# I2C_1.net
KiCad netlist of a schematic drawn in Altium Designer
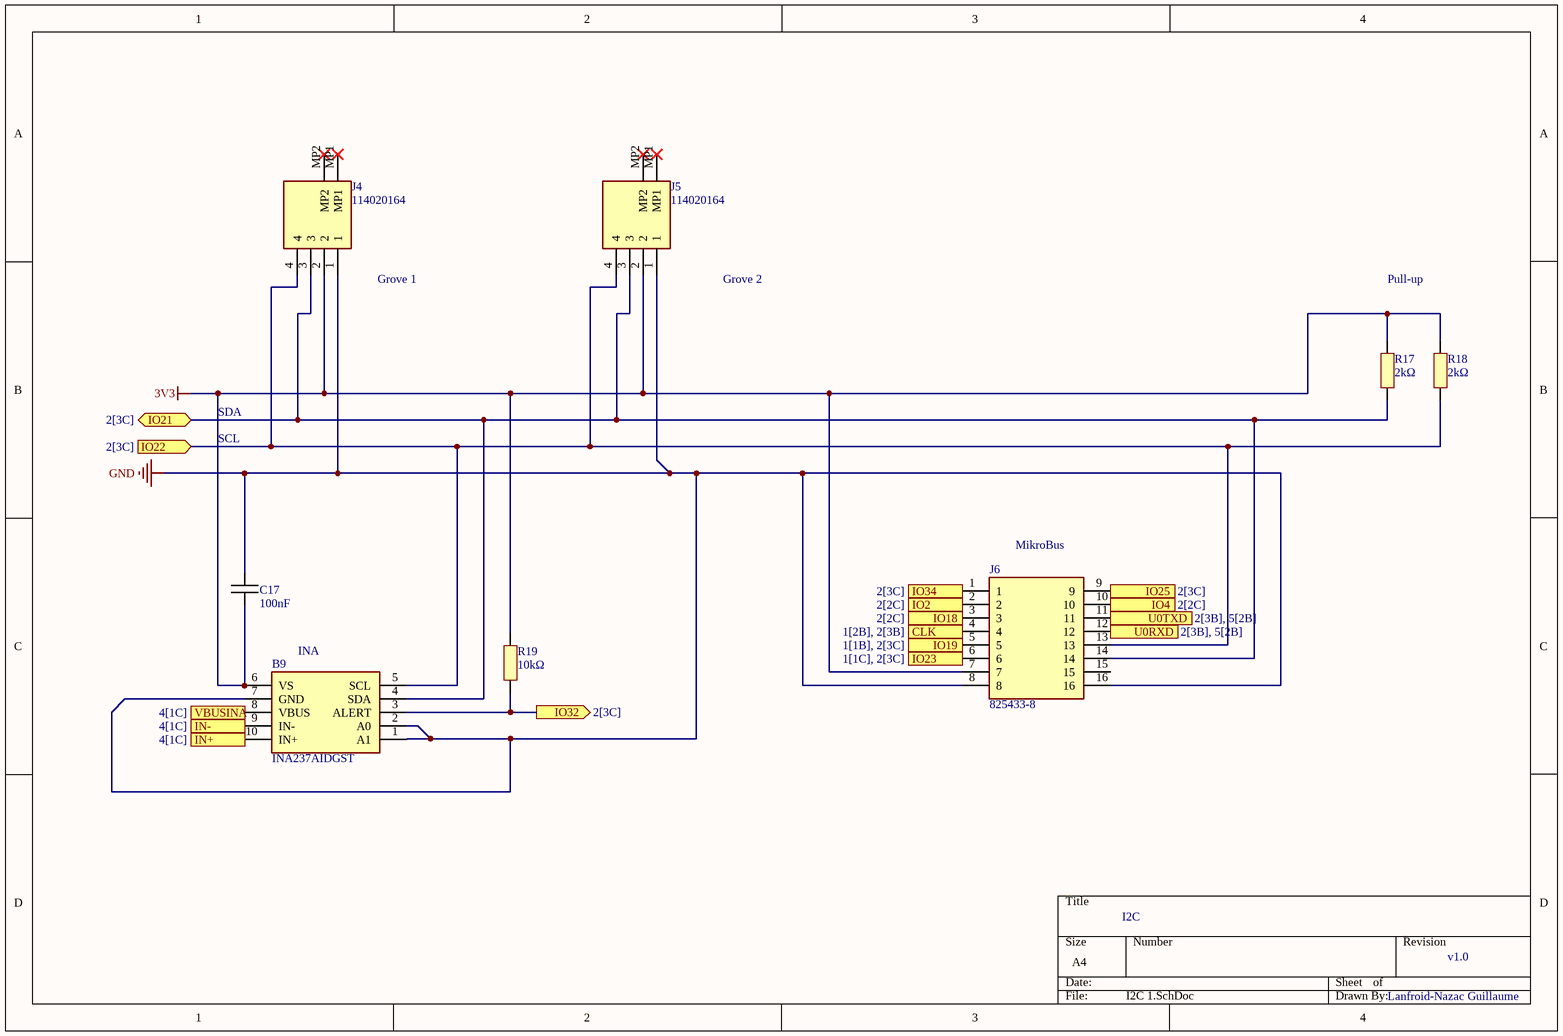
[diagram p0: I2C 1.SchDoc]

(export (version "E")
  (design (tool "Eeschema 10.0.6"))
  (components
    (comp (ref "B9")
      (value "INA237AIDGST")
      (footprint "SOP50P490X110-10N")
      (fields (field (name "MOUSER PART NUMBER") "595-INA237AIDGST"))
      (libsource (lib "SCHLibrary") (part "INA237AIDGST"))
    )
    (comp (ref "C17")
      (value "100nF")
      (footprint "CAPC1005X06N")
      (libsource (lib "SCHLibrary") (part "Capacitor"))
    )
    (comp (ref "J4")
      (value "114020164")
      (footprint "114020164")
      (description "Seeed Studio Accessories Grove Female Header - SMD-4P-2.0mm-90D-20Pcs")
      (fields (field (name "MOUSER PART NUMBER") "713-114020164"))
      (libsource (lib "SCHLibrary") (part "114020164"))
    )
    (comp (ref "J5")
      (value "114020164")
      (footprint "114020164")
      (description "Seeed Studio Accessories Grove Female Header - SMD-4P-2.0mm-90D-20Pcs")
      (fields (field (name "MOUSER PART NUMBER") "713-114020164"))
      (libsource (lib "SCHLibrary") (part "114020164"))
    )
    (comp (ref "J6")
      (value "825433-8")
      (footprint "Connect-Mikrobus")
      (description "Headers & Wire Housings 8P double for connection mikrobus")
      (fields (field (name "MOUSER PART NUMBER") "571-825433-8"))
      (libsource (lib "SCHLibrary") (part "Connect-Mikrobus"))
    )
    (comp (ref "R17")
      (value "2kΩ")
      (footprint "RESC1005X06N")
      (libsource (lib "SCHLibrary") (part "Resistor"))
    )
    (comp (ref "R18")
      (value "2kΩ")
      (footprint "RESC1005X06N")
      (libsource (lib "SCHLibrary") (part "Resistor"))
    )
    (comp (ref "R19")
      (value "10kΩ")
      (footprint "RESC1005X06N")
      (libsource (lib "SCHLibrary") (part "Resistor"))
    )
  )
  (nets
    (net (code "1") (name "/CLK") (class "Default")
      (node (ref "J6") (pin "4") (pinfunction "4_4") (pintype "passive"))
    )
    (net (code "2") (name "/IN+") (class "Default")
      (node (ref "B9") (pin "10") (pinfunction "IN+_10") (pintype "passive"))
    )
    (net (code "3") (name "/IN-") (class "Default")
      (node (ref "B9") (pin "9") (pinfunction "IN-_9") (pintype "passive"))
    )
    (net (code "4") (name "/IO2") (class "Default")
      (node (ref "J6") (pin "2") (pinfunction "2_2") (pintype "passive"))
    )
    (net (code "5") (name "/IO4") (class "Default")
      (node (ref "J6") (pin "10") (pinfunction "10_10") (pintype "passive"))
    )
    (net (code "6") (name "/IO18") (class "Default")
      (node (ref "J6") (pin "3") (pinfunction "3_3") (pintype "passive"))
    )
    (net (code "7") (name "/IO19") (class "Default")
      (node (ref "J6") (pin "5") (pinfunction "5_5") (pintype "passive"))
    )
    (net (code "8") (name "/IO21") (class "Default")
      (node (ref "B9") (pin "4") (pinfunction "SDA_4") (pintype "passive"))
      (node (ref "J4") (pin "3") (pinfunction "3_3") (pintype "passive"))
      (node (ref "J5") (pin "3") (pinfunction "3_3") (pintype "passive"))
      (node (ref "J6") (pin "14") (pinfunction "14_14") (pintype "passive"))
      (node (ref "R17") (pin "2") (pinfunction "2_2") (pintype "passive"))
    )
    (net (code "9") (name "/IO22") (class "Default")
      (node (ref "B9") (pin "5") (pinfunction "SCL_5") (pintype "passive"))
      (node (ref "J4") (pin "4") (pinfunction "4_4") (pintype "passive"))
      (node (ref "J5") (pin "4") (pinfunction "4_4") (pintype "passive"))
      (node (ref "J6") (pin "13") (pinfunction "13_13") (pintype "passive"))
      (node (ref "R18") (pin "2") (pinfunction "2_2") (pintype "passive"))
    )
    (net (code "10") (name "/IO23") (class "Default")
      (node (ref "J6") (pin "6") (pinfunction "6_6") (pintype "passive"))
    )
    (net (code "11") (name "/IO25") (class "Default")
      (node (ref "J6") (pin "9") (pinfunction "9_9") (pintype "passive"))
    )
    (net (code "12") (name "/IO32") (class "Default")
      (node (ref "B9") (pin "3") (pinfunction "ALERT_3") (pintype "passive"))
      (node (ref "R19") (pin "2") (pinfunction "2_2") (pintype "passive"))
    )
    (net (code "13") (name "/IO34") (class "Default")
      (node (ref "J6") (pin "1") (pinfunction "1_1") (pintype "passive"))
    )
    (net (code "14") (name "/U0RXD") (class "Default")
      (node (ref "J6") (pin "12") (pinfunction "12_12") (pintype "passive"))
    )
    (net (code "15") (name "/U0TXD") (class "Default")
      (node (ref "J6") (pin "11") (pinfunction "11_11") (pintype "passive"))
    )
    (net (code "16") (name "/VBUSINA") (class "Default")
      (node (ref "B9") (pin "8") (pinfunction "VBUS_8") (pintype "passive"))
    )
    (net (code "17") (name "3V3") (class "Default")
      (node (ref "B9") (pin "6") (pinfunction "VS_6") (pintype "passive"))
      (node (ref "C17") (pin "1") (pinfunction "1_1") (pintype "passive"))
      (node (ref "J4") (pin "2") (pinfunction "2_2") (pintype "passive"))
      (node (ref "J5") (pin "2") (pinfunction "2_2") (pintype "passive"))
      (node (ref "J6") (pin "7") (pinfunction "7_7") (pintype "passive"))
      (node (ref "R17") (pin "1") (pinfunction "1_1") (pintype "passive"))
      (node (ref "R18") (pin "1") (pinfunction "1_1") (pintype "passive"))
      (node (ref "R19") (pin "1") (pinfunction "1_1") (pintype "passive"))
    )
    (net (code "18") (name "GND") (class "Default")
      (node (ref "B9") (pin "1") (pinfunction "A1_1") (pintype "passive"))
      (node (ref "B9") (pin "2") (pinfunction "A0_2") (pintype "passive"))
      (node (ref "B9") (pin "7") (pinfunction "GND_7") (pintype "passive"))
      (node (ref "C17") (pin "2") (pinfunction "2_2") (pintype "passive"))
      (node (ref "J4") (pin "1") (pinfunction "1_1") (pintype "passive"))
      (node (ref "J5") (pin "1") (pinfunction "1_1") (pintype "passive"))
      (node (ref "J6") (pin "16") (pinfunction "16_16") (pintype "passive"))
      (node (ref "J6") (pin "8") (pinfunction "8_8") (pintype "passive"))
    )
    (net (code "19") (name "unconnected-(J4-PadMP1)") (class "Default")
      (node (ref "J4") (pin "MP1") (pinfunction "MP1_MP1") (pintype "passive+no_connect"))
    )
    (net (code "20") (name "unconnected-(J4-PadMP2)") (class "Default")
      (node (ref "J4") (pin "MP2") (pinfunction "MP2_MP2") (pintype "passive+no_connect"))
    )
    (net (code "21") (name "unconnected-(J5-PadMP1)") (class "Default")
      (node (ref "J5") (pin "MP1") (pinfunction "MP1_MP1") (pintype "passive+no_connect"))
    )
    (net (code "22") (name "unconnected-(J5-PadMP2)") (class "Default")
      (node (ref "J5") (pin "MP2") (pinfunction "MP2_MP2") (pintype "passive+no_connect"))
    )
    (net (code "23") (name "unconnected-(J6-Pad15)") (class "Default")
      (node (ref "J6") (pin "15") (pinfunction "15_15") (pintype "passive"))
    )
  )
)
